# E17-04-HV_MEASURE.net
KiCad netlist of a schematic drawn in Altium Designer
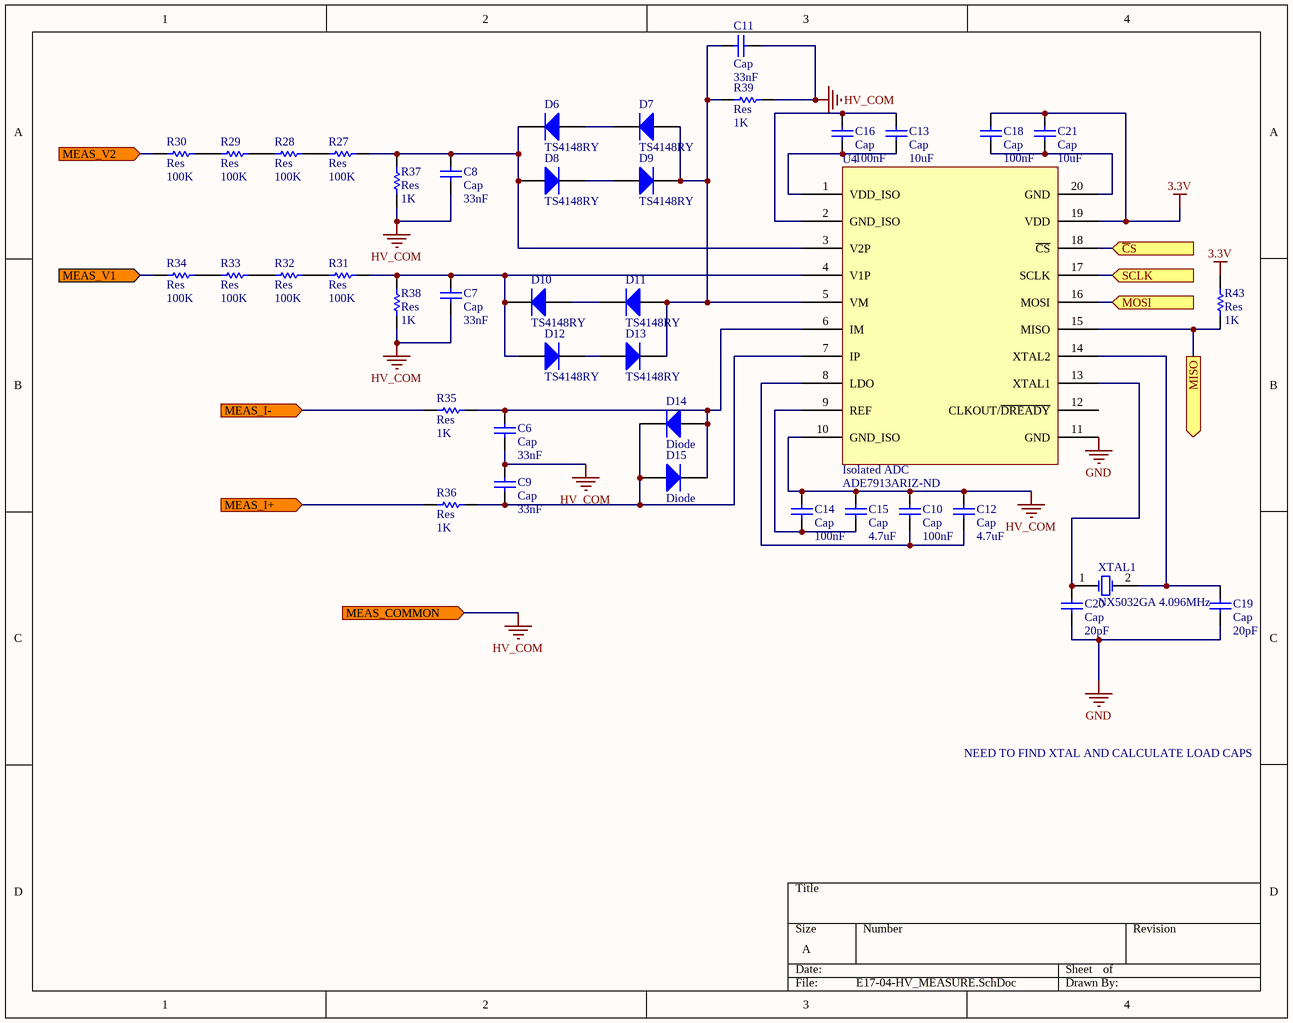
[diagram p0: E17-04-HV_MEASURE.SchDoc]

(export (version "E")
  (design (tool "Eeschema 10.0.6"))
  (components
    (comp (ref "C6")
      (value "Cap")
      (footprint "C0805")
      (description "Capacitor")
      (fields (field (name "ALTIUM_VALUE") "33nF") (field (name "PUBLISHER") "Altium Limited"))
      (libsource (lib "Capacitors") (part "Cap"))
    )
    (comp (ref "C7")
      (value "Cap")
      (footprint "C0805")
      (description "Capacitor")
      (fields (field (name "ALTIUM_VALUE") "33nF") (field (name "PUBLISHER") "Altium Limited"))
      (libsource (lib "Capacitors") (part "Cap"))
    )
    (comp (ref "C8")
      (value "Cap")
      (footprint "C0805")
      (description "Capacitor")
      (fields (field (name "ALTIUM_VALUE") "33nF") (field (name "PUBLISHER") "Altium Limited"))
      (libsource (lib "Capacitors") (part "Cap"))
    )
    (comp (ref "C9")
      (value "Cap")
      (footprint "C0805")
      (description "Capacitor")
      (fields (field (name "ALTIUM_VALUE") "33nF") (field (name "PUBLISHER") "Altium Limited"))
      (libsource (lib "Capacitors") (part "Cap"))
    )
    (comp (ref "C10")
      (value "Cap")
      (footprint "C0805")
      (description "Capacitor")
      (fields (field (name "ALTIUM_VALUE") "100nF") (field (name "PUBLISHER") "Altium Limited"))
      (libsource (lib "Capacitors") (part "Cap"))
    )
    (comp (ref "C11")
      (value "Cap")
      (footprint "C0805")
      (description "Capacitor")
      (fields (field (name "ALTIUM_VALUE") "33nF") (field (name "PUBLISHER") "Altium Limited"))
      (libsource (lib "Capacitors") (part "Cap"))
    )
    (comp (ref "C12")
      (value "Cap")
      (footprint "C0805")
      (description "Capacitor")
      (fields (field (name "ALTIUM_VALUE") "4.7uF") (field (name "PUBLISHER") "Altium Limited"))
      (libsource (lib "Capacitors") (part "Cap"))
    )
    (comp (ref "C13")
      (value "Cap")
      (footprint "C0805")
      (description "Capacitor")
      (fields (field (name "ALTIUM_VALUE") "10uF") (field (name "PUBLISHER") "Altium Limited"))
      (libsource (lib "Capacitors") (part "Cap"))
    )
    (comp (ref "C14")
      (value "Cap")
      (footprint "C0805")
      (description "Capacitor")
      (fields (field (name "ALTIUM_VALUE") "100nF") (field (name "PUBLISHER") "Altium Limited"))
      (libsource (lib "Capacitors") (part "Cap"))
    )
    (comp (ref "C15")
      (value "Cap")
      (footprint "C0805")
      (description "Capacitor")
      (fields (field (name "ALTIUM_VALUE") "4.7uF") (field (name "PUBLISHER") "Altium Limited"))
      (libsource (lib "Capacitors") (part "Cap"))
    )
    (comp (ref "C16")
      (value "Cap")
      (footprint "C0805")
      (description "Capacitor")
      (fields (field (name "ALTIUM_VALUE") "100nF") (field (name "PUBLISHER") "Altium Limited"))
      (libsource (lib "Capacitors") (part "Cap"))
    )
    (comp (ref "C18")
      (value "Cap")
      (footprint "C0805")
      (description "Capacitor")
      (fields (field (name "ALTIUM_VALUE") "100nF") (field (name "PUBLISHER") "Altium Limited"))
      (libsource (lib "Capacitors") (part "Cap"))
    )
    (comp (ref "C19")
      (value "Cap")
      (footprint "C0805")
      (description "Capacitor")
      (fields (field (name "ALTIUM_VALUE") "20pF") (field (name "PUBLISHER") "Altium Limited"))
      (libsource (lib "Capacitors") (part "Cap"))
    )
    (comp (ref "C20")
      (value "Cap")
      (footprint "C0805")
      (description "Capacitor")
      (fields (field (name "ALTIUM_VALUE") "20pF") (field (name "PUBLISHER") "Altium Limited"))
      (libsource (lib "Capacitors") (part "Cap"))
    )
    (comp (ref "C21")
      (value "Cap")
      (footprint "C0805")
      (description "Capacitor")
      (fields (field (name "ALTIUM_VALUE") "10uF") (field (name "PUBLISHER") "Altium Limited"))
      (libsource (lib "Capacitors") (part "Cap"))
    )
    (comp (ref "D6")
      (value "TS4148RY")
      (footprint "DIOC2012X09N")
      (description "Default Diode")
      (fields (field (name "PUBLISHER") "Altium Limited"))
      (libsource (lib "") (part "Diode_2"))
    )
    (comp (ref "D7")
      (value "TS4148RY")
      (footprint "DIOC2012X09N")
      (description "Default Diode")
      (fields (field (name "PUBLISHER") "Altium Limited"))
      (libsource (lib "Miscellaneous Devices") (part "Diode"))
    )
    (comp (ref "D8")
      (value "TS4148RY")
      (footprint "DIOC2012X09N")
      (description "Default Diode")
      (fields (field (name "PUBLISHER") "Altium Limited"))
      (libsource (lib "") (part "Diode_1"))
    )
    (comp (ref "D9")
      (value "TS4148RY")
      (footprint "DIOC2012X09N")
      (description "Default Diode")
      (fields (field (name "PUBLISHER") "Altium Limited"))
      (libsource (lib "Miscellaneous Devices") (part "Diode"))
    )
    (comp (ref "D10")
      (value "TS4148RY")
      (footprint "DIOC2012X09N")
      (description "Default Diode")
      (fields (field (name "PUBLISHER") "Altium Limited"))
      (libsource (lib "") (part "Diode_2"))
    )
    (comp (ref "D11")
      (value "TS4148RY")
      (footprint "DIOC2012X09N")
      (description "Default Diode")
      (fields (field (name "PUBLISHER") "Altium Limited"))
      (libsource (lib "Miscellaneous Devices") (part "Diode"))
    )
    (comp (ref "D12")
      (value "TS4148RY")
      (footprint "DIOC2012X09N")
      (description "Default Diode")
      (fields (field (name "PUBLISHER") "Altium Limited"))
      (libsource (lib "Miscellaneous Devices") (part "Diode"))
    )
    (comp (ref "D13")
      (value "TS4148RY")
      (footprint "DIOC2012X09N")
      (description "Default Diode")
      (fields (field (name "PUBLISHER") "Altium Limited"))
      (libsource (lib "Miscellaneous Devices") (part "Diode"))
    )
    (comp (ref "D14")
      (value "Diode")
      (footprint "SMC")
      (description "Default Diode")
      (fields (field (name "PUBLISHER") "Altium Limited"))
      (libsource (lib "Miscellaneous Devices") (part "Diode"))
    )
    (comp (ref "D15")
      (value "Diode")
      (footprint "SMC")
      (description "Default Diode")
      (fields (field (name "PUBLISHER") "Altium Limited"))
      (libsource (lib "Miscellaneous Devices") (part "Diode"))
    )
    (comp (ref "R27")
      (value "Res")
      (footprint "3216[1206]")
      (description "Surface Mount Resistor")
      (fields (field (name "ALTIUM_VALUE") "100K") (field (name "PUBLISHER") "Altium Limited"))
      (libsource (lib "Resistors") (part "Res"))
    )
    (comp (ref "R28")
      (value "Res")
      (footprint "3216[1206]")
      (description "Surface Mount Resistor")
      (fields (field (name "ALTIUM_VALUE") "100K") (field (name "PUBLISHER") "Altium Limited"))
      (libsource (lib "Resistors") (part "Res"))
    )
    (comp (ref "R29")
      (value "Res")
      (footprint "3216[1206]")
      (description "Surface Mount Resistor")
      (fields (field (name "ALTIUM_VALUE") "100K") (field (name "PUBLISHER") "Altium Limited"))
      (libsource (lib "Resistors") (part "Res"))
    )
    (comp (ref "R30")
      (value "Res")
      (footprint "3216[1206]")
      (description "Surface Mount Resistor")
      (fields (field (name "ALTIUM_VALUE") "100K") (field (name "PUBLISHER") "Altium Limited"))
      (libsource (lib "Resistors") (part "Res"))
    )
    (comp (ref "R31")
      (value "Res")
      (footprint "3216[1206]")
      (description "Surface Mount Resistor")
      (fields (field (name "ALTIUM_VALUE") "100K") (field (name "PUBLISHER") "Altium Limited"))
      (libsource (lib "Resistors") (part "Res"))
    )
    (comp (ref "R32")
      (value "Res")
      (footprint "3216[1206]")
      (description "Surface Mount Resistor")
      (fields (field (name "ALTIUM_VALUE") "100K") (field (name "PUBLISHER") "Altium Limited"))
      (libsource (lib "Resistors") (part "Res"))
    )
    (comp (ref "R33")
      (value "Res")
      (footprint "3216[1206]")
      (description "Surface Mount Resistor")
      (fields (field (name "ALTIUM_VALUE") "100K") (field (name "PUBLISHER") "Altium Limited"))
      (libsource (lib "Resistors") (part "Res"))
    )
    (comp (ref "R34")
      (value "Res")
      (footprint "3216[1206]")
      (description "Surface Mount Resistor")
      (fields (field (name "ALTIUM_VALUE") "100K") (field (name "PUBLISHER") "Altium Limited"))
      (libsource (lib "Resistors") (part "Res"))
    )
    (comp (ref "R35")
      (value "Res")
      (footprint "2012[0805]")
      (description "Surface Mount Resistor")
      (fields (field (name "ALTIUM_VALUE") "1K") (field (name "PUBLISHER") "Altium Limited"))
      (libsource (lib "Resistors") (part "Res"))
    )
    (comp (ref "R36")
      (value "Res")
      (footprint "2012[0805]")
      (description "Surface Mount Resistor")
      (fields (field (name "ALTIUM_VALUE") "1K") (field (name "PUBLISHER") "Altium Limited"))
      (libsource (lib "Resistors") (part "Res"))
    )
    (comp (ref "R37")
      (value "Res")
      (footprint "2012[0805]")
      (description "Surface Mount Resistor")
      (fields (field (name "ALTIUM_VALUE") "1K") (field (name "PUBLISHER") "Altium Limited"))
      (libsource (lib "Resistors") (part "Res"))
    )
    (comp (ref "R38")
      (value "Res")
      (footprint "2012[0805]")
      (description "Surface Mount Resistor")
      (fields (field (name "ALTIUM_VALUE") "1K") (field (name "PUBLISHER") "Altium Limited"))
      (libsource (lib "Resistors") (part "Res"))
    )
    (comp (ref "R39")
      (value "Res")
      (footprint "2012[0805]")
      (description "Surface Mount Resistor")
      (fields (field (name "ALTIUM_VALUE") "1K") (field (name "PUBLISHER") "Altium Limited"))
      (libsource (lib "Resistors") (part "Res"))
    )
    (comp (ref "R43")
      (value "Res")
      (footprint "2012[0805]")
      (description "Surface Mount Resistor")
      (fields (field (name "ALTIUM_VALUE") "1K") (field (name "PUBLISHER") "Altium Limited"))
      (libsource (lib "Resistors") (part "Res"))
    )
    (comp (ref "U4")
      (value "Isolated ADC")
      (footprint "SOIC127P1030X265-20N")
      (description "3-Channel, Isolated, Sigma Delta ADC with SPI")
      (fields (field (name "SUPPLIER PART NUMBER 1") "ADE7913ARIZ-ND"))
      (libsource (lib "Isolation_Circuits") (part "ADE7913"))
    )
    (comp (ref "XTAL1")
      (value "NX5032GA 4.096MHz")
      (footprint "NX5032GA")
      (description "NX5032GA")
      (libsource (lib "Crystal Oscillators") (part "NX5032GA"))
    )
  )
  (nets
    (net (code "1") (name "/MEAS_I+") (class "Default")
      (node (ref "R36") (pin "2") (pinfunction "2_2") (pintype "passive"))
    )
    (net (code "2") (name "/MEAS_I-") (class "Default")
      (node (ref "R35") (pin "2") (pinfunction "2_2") (pintype "passive"))
    )
    (net (code "3") (name "/MEAS_V1") (class "Default")
      (node (ref "R34") (pin "1") (pinfunction "1_1") (pintype "passive"))
    )
    (net (code "4") (name "/MEAS_V2") (class "Default")
      (node (ref "R30") (pin "1") (pinfunction "1_1") (pintype "passive"))
    )
    (net (code "5") (name "/MISO") (class "Default")
      (node (ref "R43") (pin "2") (pinfunction "2_2") (pintype "passive"))
      (node (ref "U4") (pin "15") (pinfunction "MISO_15") (pintype "passive"))
    )
    (net (code "6") (name "/MOSI") (class "Default")
      (node (ref "U4") (pin "16") (pinfunction "MOSI_16") (pintype "passive"))
    )
    (net (code "7") (name "/SCLK") (class "Default")
      (node (ref "U4") (pin "17") (pinfunction "SCLK_17") (pintype "passive"))
    )
    (net (code "8") (name "/~{C}S") (class "Default")
      (node (ref "U4") (pin "18") (pinfunction "~{CS}_18") (pintype "passive"))
    )
    (net (code "9") (name "3.3V") (class "Default")
      (node (ref "C18") (pin "1") (pinfunction "1_1") (pintype "passive"))
      (node (ref "C21") (pin "1") (pinfunction "1_1") (pintype "passive"))
      (node (ref "R43") (pin "1") (pinfunction "1_1") (pintype "passive"))
      (node (ref "U4") (pin "19") (pinfunction "VDD_19") (pintype "passive"))
    )
    (net (code "10") (name "GND") (class "Default")
      (node (ref "C19") (pin "1") (pinfunction "1_1") (pintype "passive"))
      (node (ref "C20") (pin "1") (pinfunction "1_1") (pintype "passive"))
      (node (ref "U4") (pin "11") (pinfunction "GND_11") (pintype "passive"))
    )
    (net (code "11") (name "HV_COM") (class "Default")
      (node (ref "C10") (pin "1") (pinfunction "1_1") (pintype "passive"))
      (node (ref "C11") (pin "1") (pinfunction "1_1") (pintype "passive"))
      (node (ref "C12") (pin "1") (pinfunction "1_1") (pintype "passive"))
      (node (ref "C14") (pin "1") (pinfunction "1_1") (pintype "passive"))
      (node (ref "C15") (pin "1") (pinfunction "1_1") (pintype "passive"))
      (node (ref "C6") (pin "1") (pinfunction "1_1") (pintype "passive"))
      (node (ref "C7") (pin "1") (pinfunction "1_1") (pintype "passive"))
      (node (ref "C8") (pin "1") (pinfunction "1_1") (pintype "passive"))
      (node (ref "C9") (pin "2") (pinfunction "2_2") (pintype "passive"))
      (node (ref "R37") (pin "1") (pinfunction "1_1") (pintype "passive"))
      (node (ref "R38") (pin "1") (pinfunction "1_1") (pintype "passive"))
      (node (ref "R39") (pin "1") (pinfunction "1_1") (pintype "passive"))
      (node (ref "U4") (pin "10") (pinfunction "GND_ISO_10") (pintype "passive"))
    )
    (net (code "12") (name "Net-(C13-Pad1)") (class "Default")
      (node (ref "C13") (pin "1") (pinfunction "1_1") (pintype "passive"))
      (node (ref "C16") (pin "1") (pinfunction "1_1") (pintype "passive"))
      (node (ref "U4") (pin "2") (pinfunction "GND_ISO_2") (pintype "passive"))
    )
    (net (code "13") (name "Net-(C18-Pad2)") (class "Default")
      (node (ref "C18") (pin "2") (pinfunction "2_2") (pintype "passive"))
      (node (ref "C21") (pin "2") (pinfunction "2_2") (pintype "passive"))
      (node (ref "U4") (pin "20") (pinfunction "GND_20") (pintype "passive"))
    )
    (net (code "14") (name "Net-(D6-K)") (class "Default")
      (node (ref "D6") (pin "2") (pinfunction "K_2") (pintype "passive"))
      (node (ref "D7") (pin "2") (pinfunction "K_2") (pintype "passive"))
    )
    (net (code "15") (name "Net-(D6-K)_1") (class "Default")
      (node (ref "C8") (pin "2") (pinfunction "2_2") (pintype "passive"))
      (node (ref "D6") (pin "2") (pinfunction "K_2") (pintype "passive"))
      (node (ref "D8") (pin "1") (pinfunction "A_1") (pintype "passive"))
      (node (ref "R27") (pin "2") (pinfunction "2_2") (pintype "passive"))
      (node (ref "R37") (pin "2") (pinfunction "2_2") (pintype "passive"))
      (node (ref "U4") (pin "3") (pinfunction "V2P_3") (pintype "passive"))
    )
    (net (code "16") (name "Net-(D8-A)") (class "Default")
      (node (ref "D8") (pin "1") (pinfunction "A_1") (pintype "passive"))
      (node (ref "D9") (pin "1") (pinfunction "A_1") (pintype "passive"))
    )
    (net (code "17") (name "Net-(D10-K)") (class "Default")
      (node (ref "D10") (pin "2") (pinfunction "K_2") (pintype "passive"))
      (node (ref "D11") (pin "2") (pinfunction "K_2") (pintype "passive"))
    )
    (net (code "18") (name "Net-(D10-K)_1") (class "Default")
      (node (ref "C7") (pin "2") (pinfunction "2_2") (pintype "passive"))
      (node (ref "D10") (pin "2") (pinfunction "K_2") (pintype "passive"))
      (node (ref "D12") (pin "1") (pinfunction "A_1") (pintype "passive"))
      (node (ref "R31") (pin "2") (pinfunction "2_2") (pintype "passive"))
      (node (ref "R38") (pin "2") (pinfunction "2_2") (pintype "passive"))
      (node (ref "U4") (pin "4") (pinfunction "V1P_4") (pintype "passive"))
    )
    (net (code "19") (name "Net-(D11-A)") (class "Default")
      (node (ref "C11") (pin "2") (pinfunction "2_2") (pintype "passive"))
      (node (ref "D11") (pin "1") (pinfunction "A_1") (pintype "passive"))
      (node (ref "D13") (pin "2") (pinfunction "K_2") (pintype "passive"))
      (node (ref "D7") (pin "1") (pinfunction "A_1") (pintype "passive"))
      (node (ref "D9") (pin "2") (pinfunction "K_2") (pintype "passive"))
      (node (ref "R39") (pin "2") (pinfunction "2_2") (pintype "passive"))
      (node (ref "U4") (pin "5") (pinfunction "VM_5") (pintype "passive"))
    )
    (net (code "20") (name "Net-(D12-K)") (class "Default")
      (node (ref "D12") (pin "2") (pinfunction "K_2") (pintype "passive"))
      (node (ref "D13") (pin "1") (pinfunction "A_1") (pintype "passive"))
    )
    (net (code "21") (name "Net-(D14-A)") (class "Default")
      (node (ref "C6") (pin "2") (pinfunction "2_2") (pintype "passive"))
      (node (ref "D14") (pin "1") (pinfunction "A_1") (pintype "passive"))
      (node (ref "D15") (pin "2") (pinfunction "K_2") (pintype "passive"))
      (node (ref "R35") (pin "1") (pinfunction "1_1") (pintype "passive"))
      (node (ref "U4") (pin "6") (pinfunction "IM_6") (pintype "passive"))
    )
    (net (code "22") (name "Net-(D14-K)") (class "Default")
      (node (ref "C9") (pin "1") (pinfunction "1_1") (pintype "passive"))
      (node (ref "D14") (pin "2") (pinfunction "K_2") (pintype "passive"))
      (node (ref "D15") (pin "1") (pinfunction "A_1") (pintype "passive"))
      (node (ref "R36") (pin "1") (pinfunction "1_1") (pintype "passive"))
      (node (ref "U4") (pin "7") (pinfunction "IP_7") (pintype "passive"))
    )
    (net (code "23") (name "Net-(R27-Pad1)") (class "Default")
      (node (ref "R27") (pin "1") (pinfunction "1_1") (pintype "passive"))
      (node (ref "R28") (pin "2") (pinfunction "2_2") (pintype "passive"))
    )
    (net (code "24") (name "Net-(R28-Pad1)") (class "Default")
      (node (ref "R28") (pin "1") (pinfunction "1_1") (pintype "passive"))
      (node (ref "R29") (pin "2") (pinfunction "2_2") (pintype "passive"))
    )
    (net (code "25") (name "Net-(R29-Pad1)") (class "Default")
      (node (ref "R29") (pin "1") (pinfunction "1_1") (pintype "passive"))
      (node (ref "R30") (pin "2") (pinfunction "2_2") (pintype "passive"))
    )
    (net (code "26") (name "Net-(R31-Pad1)") (class "Default")
      (node (ref "R31") (pin "1") (pinfunction "1_1") (pintype "passive"))
      (node (ref "R32") (pin "2") (pinfunction "2_2") (pintype "passive"))
    )
    (net (code "27") (name "Net-(R32-Pad1)") (class "Default")
      (node (ref "R32") (pin "1") (pinfunction "1_1") (pintype "passive"))
      (node (ref "R33") (pin "2") (pinfunction "2_2") (pintype "passive"))
    )
    (net (code "28") (name "Net-(R33-Pad1)") (class "Default")
      (node (ref "R33") (pin "1") (pinfunction "1_1") (pintype "passive"))
      (node (ref "R34") (pin "2") (pinfunction "2_2") (pintype "passive"))
    )
    (net (code "29") (name "Net-(U4-LDO)") (class "Default")
      (node (ref "C10") (pin "2") (pinfunction "2_2") (pintype "passive"))
      (node (ref "C12") (pin "2") (pinfunction "2_2") (pintype "passive"))
      (node (ref "U4") (pin "8") (pinfunction "LDO_8") (pintype "passive"))
    )
    (net (code "30") (name "Net-(U4-REF)") (class "Default")
      (node (ref "C14") (pin "2") (pinfunction "2_2") (pintype "passive"))
      (node (ref "C15") (pin "2") (pinfunction "2_2") (pintype "passive"))
      (node (ref "U4") (pin "9") (pinfunction "REF_9") (pintype "passive"))
    )
    (net (code "31") (name "Net-(U4-VDD_ISO)") (class "Default")
      (node (ref "C13") (pin "2") (pinfunction "2_2") (pintype "passive"))
      (node (ref "C16") (pin "2") (pinfunction "2_2") (pintype "passive"))
      (node (ref "U4") (pin "1") (pinfunction "VDD_ISO_1") (pintype "passive"))
    )
    (net (code "32") (name "Net-(U4-XTAL1)") (class "Default")
      (node (ref "C20") (pin "2") (pinfunction "2_2") (pintype "passive"))
      (node (ref "U4") (pin "13") (pinfunction "XTAL1_13") (pintype "passive"))
      (node (ref "XTAL1") (pin "1") (pinfunction "OSC1_1") (pintype "passive"))
    )
    (net (code "33") (name "Net-(U4-XTAL2)") (class "Default")
      (node (ref "C19") (pin "2") (pinfunction "2_2") (pintype "passive"))
      (node (ref "U4") (pin "14") (pinfunction "XTAL2_14") (pintype "passive"))
      (node (ref "XTAL1") (pin "2") (pinfunction "OSC2_2") (pintype "passive"))
    )
    (net (code "34") (name "unconnected-(U4-CLKOUT{slash}~{DREADY}-Pad12)") (class "Default")
      (node (ref "U4") (pin "12") (pinfunction "CLKOUT/~{DREADY}_12") (pintype "passive"))
    )
  )
)
